# NANO_STM32F103_1.net
KiCad netlist of a schematic drawn in Altium Designer
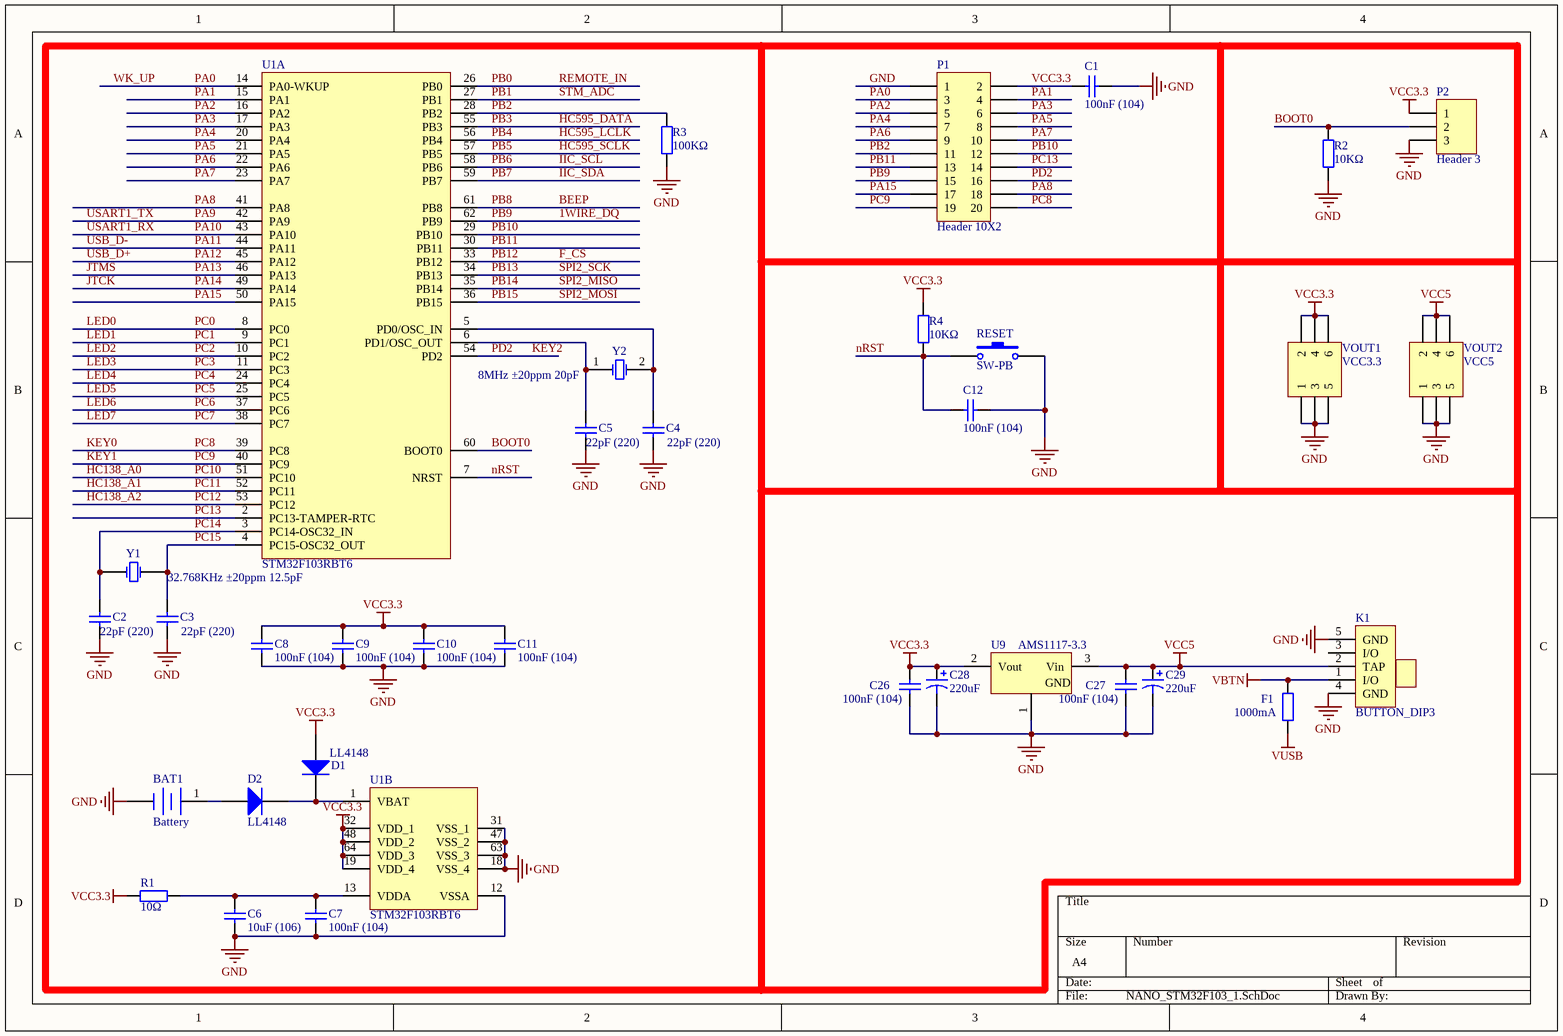
[diagram p0: NANO_STM32F103_1.SchDoc]

(export (version "E")
  (design (tool "Eeschema 10.0.6"))
  (components
    (comp (ref "BAT1")
      (value "Battery")
      (footprint "NANO_STM32F103:BAT-2")
      (description "Multicell Battery")
      (fields (field (name "PUBLISHER") "Altium Limited"))
      (libsource (lib "Miscellaneous Devices") (part "Battery"))
    )
    (comp (ref "C1")
      (value "100nF (104)")
      (footprint "NANO_STM32F103:0603_C")
      (description "贴片电容")
      (libsource (lib "Miscellaneous Devices LC") (part "0603 100nF (104) 10% 50V"))
    )
    (comp (ref "C2")
      (value "22pF (220)")
      (footprint "NANO_STM32F103:0603_C")
      (description "贴片电容")
      (libsource (lib "Miscellaneous Devices LC") (part "0603 22pF (220) 5% 50V"))
    )
    (comp (ref "C3")
      (value "22pF (220)")
      (footprint "NANO_STM32F103:0603_C")
      (description "贴片电容")
      (libsource (lib "Miscellaneous Devices LC") (part "0603 22pF (220) 5% 50V"))
    )
    (comp (ref "C4")
      (value "22pF (220)")
      (footprint "NANO_STM32F103:0603_C")
      (description "贴片电容")
      (libsource (lib "Miscellaneous Devices LC") (part "0603 22pF (220) 5% 50V"))
    )
    (comp (ref "C5")
      (value "22pF (220)")
      (footprint "NANO_STM32F103:0603_C")
      (description "贴片电容")
      (libsource (lib "Miscellaneous Devices LC") (part "0603 22pF (220) 5% 50V"))
    )
    (comp (ref "C6")
      (value "10uF (106)")
      (footprint "NANO_STM32F103:0805_C")
      (description "贴片电容")
      (libsource (lib "Miscellaneous Devices LC") (part "0805 10uF (106) 10% 25V"))
    )
    (comp (ref "C7")
      (value "100nF (104)")
      (footprint "NANO_STM32F103:0603_C")
      (description "贴片电容")
      (libsource (lib "Miscellaneous Devices LC") (part "0603 100nF (104) 10% 50V"))
    )
    (comp (ref "C8")
      (value "100nF (104)")
      (footprint "NANO_STM32F103:0603_C")
      (description "贴片电容")
      (libsource (lib "Miscellaneous Devices LC") (part "0603 100nF (104) 10% 50V"))
    )
    (comp (ref "C9")
      (value "100nF (104)")
      (footprint "NANO_STM32F103:0603_C")
      (description "贴片电容")
      (libsource (lib "Miscellaneous Devices LC") (part "0603 100nF (104) 10% 50V"))
    )
    (comp (ref "C10")
      (value "100nF (104)")
      (footprint "NANO_STM32F103:0603_C")
      (description "贴片电容")
      (libsource (lib "Miscellaneous Devices LC") (part "0603 100nF (104) 10% 50V"))
    )
    (comp (ref "C11")
      (value "100nF (104)")
      (footprint "NANO_STM32F103:0603_C")
      (description "贴片电容")
      (libsource (lib "Miscellaneous Devices LC") (part "0603 100nF (104) 10% 50V"))
    )
    (comp (ref "C12")
      (value "100nF (104)")
      (footprint "NANO_STM32F103:0603_C")
      (description "贴片电容")
      (libsource (lib "Miscellaneous Devices LC") (part "0603 100nF (104) 10% 50V"))
    )
    (comp (ref "C26")
      (value "100nF (104)")
      (footprint "NANO_STM32F103:0603_C")
      (description "贴片电容")
      (libsource (lib "Miscellaneous Devices LC") (part "0603 100nF (104) 10% 50V"))
    )
    (comp (ref "C27")
      (value "100nF (104)")
      (footprint "NANO_STM32F103:0603_C")
      (description "贴片电容")
      (libsource (lib "Miscellaneous Devices LC") (part "0603 100nF (104) 10% 50V"))
    )
    (comp (ref "C28")
      (value "220uF")
      (footprint "NANO_STM32F103:RB7.6-15")
      (description "电解电容")
      (fields (field (name "PUBLISHER") "Altium Limited"))
      (libsource (lib "Miscellaneous Devices") (part "Cap Pol1"))
    )
    (comp (ref "C29")
      (value "220uF")
      (footprint "NANO_STM32F103:RB7.6-15")
      (description "电解电容")
      (fields (field (name "PUBLISHER") "Altium Limited"))
      (libsource (lib "Miscellaneous Devices") (part "Cap Pol1"))
    )
    (comp (ref "D1")
      (value "LL4148")
      (footprint "NANO_STM32F103:LL-34")
      (description "开关二极管")
      (libsource (lib "Miscellaneous Devices LC") (part "LL-34 LL4148 LL-34 1206"))
    )
    (comp (ref "D2")
      (value "LL4148")
      (footprint "NANO_STM32F103:LL-34")
      (description "开关二极管")
      (libsource (lib "Miscellaneous Devices LC") (part "LL-34 LL4148 LL-34 1206"))
    )
    (comp (ref "F1")
      (value "1000mA")
      (footprint "NANO_STM32F103:0805_R")
      (description "自恢复保险丝")
      (libsource (lib "Miscellaneous Devices LC") (part "0805 1KΩ (1001) 1%"))
    )
    (comp (ref "K1")
      (value "BUTTON_DIP3")
      (footprint "NANO_STM32F103:SW")
      (description "拨动开关")
      (libsource (lib "NANO_STM32F103") (part "BUTTON_DIP3"))
    )
    (comp (ref "P1")
      (value "Header 10X2")
      (footprint "NANO_STM32F103:HDR2X10")
      (description "Header, 10-Pin, Dual row")
      (fields (field (name "PUBLISHER") "Altium Limited"))
      (libsource (lib "Miscellaneous Connectors") (part "Header 10X2"))
    )
    (comp (ref "P2")
      (value "Header 3")
      (footprint "NANO_STM32F103:HDR1X3")
      (description "Header, 3-Pin")
      (fields (field (name "PUBLISHER") "Altium Limited"))
      (libsource (lib "Miscellaneous Connectors") (part "Header 3"))
    )
    (comp (ref "R1")
      (value "10Ω")
      (footprint "NANO_STM32F103:0603_R")
      (description "贴片电阻")
      (libsource (lib "Miscellaneous Devices LC") (part "0603 10Ω (10R0) 1%"))
    )
    (comp (ref "R2")
      (value "10KΩ")
      (footprint "0603_R")
      (description "贴片电阻")
      (libsource (lib "NANO_STM32F103_2") (part "0603 10KΩ (1002) 1%"))
    )
    (comp (ref "R3")
      (value "100KΩ")
      (footprint "NANO_STM32F103:0603_R")
      (description "贴片电阻")
      (libsource (lib "Miscellaneous Devices LC") (part "0603 100KΩ (1003) 1%"))
    )
    (comp (ref "R4")
      (value "10KΩ")
      (footprint "NANO_STM32F103:0603_R")
      (description "贴片电阻")
      (libsource (lib "Miscellaneous Devices LC") (part "0603 10KΩ (1002) 1%"))
    )
    (comp (ref "RESET")
      (value "SW-PB")
      (footprint "NANO_STM32F103:SPST-2")
      (description "RESET")
      (fields (field (name "PUBLISHER") "Altium Limited"))
      (libsource (lib "Miscellaneous Devices") (part "SW-PB"))
    )
    (comp (ref "U1")
      (value "STM32F103RBT6")
      (footprint "NANO_STM32F103:LQFP-64_10x10x05P")
      (description "ARM")
      (libsource (lib "Miscellaneous Devices LC") (part "STM32F103RBT6"))
    )
    (comp (ref "U9")
      (value "AMS1117-3.3")
      (footprint "NANO_STM32F103:SOT-223")
      (description "低压差线性稳压(LDO)")
      (libsource (lib "Miscellaneous Devices LC") (part "SOT-223 AMS1117-3.3"))
    )
    (comp (ref "VOUT1")
      (value "VCC3.3")
      (footprint "NANO_STM32F103:HDR2X3")
      (description "Header, 3-Pin, Dual row")
      (fields (field (name "PUBLISHER") "Altium Limited"))
      (libsource (lib "Miscellaneous Connectors") (part "Header 3X2"))
    )
    (comp (ref "VOUT2")
      (value "VCC5")
      (footprint "NANO_STM32F103:HDR2X3")
      (description "Header, 3-Pin, Dual row")
      (fields (field (name "PUBLISHER") "Altium Limited"))
      (libsource (lib "Miscellaneous Connectors") (part "Header 3X2"))
    )
    (comp (ref "Y1")
      (value "32.768KHz ±20ppm 12.5pF")
      (footprint "NANO_STM32F103:SMD-3215_2P FC - 135")
      (description "贴片晶振")
      (libsource (lib "Miscellaneous Devices LC") (part "SMD-3215_2P 32.768KHz 20ppm 12.5pF"))
    )
    (comp (ref "Y2")
      (value "8MHz ±20ppm 20pF")
      (footprint "NANO_STM32F103:SMD-5032_2P")
      (description "贴片晶振")
      (libsource (lib "Miscellaneous Devices LC") (part "SMD-5032_2P 8MHz 20ppm 20pF"))
    )
  )
  (nets
    (net (code "1") (name "/1WIRE_DQ") (class "Default")
      (node (ref "P1") (pin "15") (pinfunction "15_15") (pintype "passive"))
      (node (ref "U1") (pin "62") (pinfunction "PB9_62") (pintype "passive"))
    )
    (net (code "2") (name "/BEEP") (class "Default")
      (node (ref "U1") (pin "61") (pinfunction "PB8_61") (pintype "passive"))
    )
    (net (code "3") (name "/BOOT0") (class "Default")
      (node (ref "P2") (pin "2") (pinfunction "2_2") (pintype "passive"))
      (node (ref "R2") (pin "2") (pinfunction "2_2") (pintype "passive"))
      (node (ref "U1") (pin "60") (pinfunction "BOOT0_60") (pintype "passive"))
    )
    (net (code "4") (name "/F_CS") (class "Default")
      (node (ref "U1") (pin "33") (pinfunction "PB12_33") (pintype "passive"))
    )
    (net (code "5") (name "/HC138_A0") (class "Default")
      (node (ref "U1") (pin "51") (pinfunction "PC10_51") (pintype "passive"))
    )
    (net (code "6") (name "/HC138_A1") (class "Default")
      (node (ref "U1") (pin "52") (pinfunction "PC11_52") (pintype "passive"))
    )
    (net (code "7") (name "/HC138_A2") (class "Default")
      (node (ref "U1") (pin "53") (pinfunction "PC12_53") (pintype "passive"))
    )
    (net (code "8") (name "/HC595_DATA") (class "Default")
      (node (ref "U1") (pin "55") (pinfunction "PB3_55") (pintype "passive"))
    )
    (net (code "9") (name "/HC595_LCLK") (class "Default")
      (node (ref "U1") (pin "56") (pinfunction "PB4_56") (pintype "passive"))
    )
    (net (code "10") (name "/HC595_SCLK") (class "Default")
      (node (ref "U1") (pin "57") (pinfunction "PB5_57") (pintype "passive"))
    )
    (net (code "11") (name "/IIC_SCL") (class "Default")
      (node (ref "U1") (pin "58") (pinfunction "PB6_58") (pintype "passive"))
    )
    (net (code "12") (name "/IIC_SDA") (class "Default")
      (node (ref "U1") (pin "59") (pinfunction "PB7_59") (pintype "passive"))
    )
    (net (code "13") (name "/JTCK") (class "Default")
      (node (ref "U1") (pin "49") (pinfunction "PA14_49") (pintype "passive"))
    )
    (net (code "14") (name "/JTMS") (class "Default")
      (node (ref "U1") (pin "46") (pinfunction "PA13_46") (pintype "passive"))
    )
    (net (code "15") (name "/KEY0") (class "Default")
      (node (ref "P1") (pin "20") (pinfunction "20_20") (pintype "passive"))
      (node (ref "U1") (pin "39") (pinfunction "PC8_39") (pintype "passive"))
    )
    (net (code "16") (name "/KEY1") (class "Default")
      (node (ref "P1") (pin "19") (pinfunction "19_19") (pintype "passive"))
      (node (ref "U1") (pin "40") (pinfunction "PC9_40") (pintype "passive"))
    )
    (net (code "17") (name "/KEY2") (class "Default")
      (node (ref "P1") (pin "16") (pinfunction "16_16") (pintype "passive"))
      (node (ref "U1") (pin "54") (pinfunction "PD2_54") (pintype "passive"))
    )
    (net (code "18") (name "/LED0") (class "Default")
      (node (ref "U1") (pin "8") (pinfunction "PC0_8") (pintype "passive"))
    )
    (net (code "19") (name "/LED1") (class "Default")
      (node (ref "U1") (pin "9") (pinfunction "PC1_9") (pintype "passive"))
    )
    (net (code "20") (name "/LED2") (class "Default")
      (node (ref "U1") (pin "10") (pinfunction "PC2_10") (pintype "passive"))
    )
    (net (code "21") (name "/LED3") (class "Default")
      (node (ref "U1") (pin "11") (pinfunction "PC3_11") (pintype "passive"))
    )
    (net (code "22") (name "/LED4") (class "Default")
      (node (ref "U1") (pin "24") (pinfunction "PC4_24") (pintype "passive"))
    )
    (net (code "23") (name "/LED5") (class "Default")
      (node (ref "U1") (pin "25") (pinfunction "PC5_25") (pintype "passive"))
    )
    (net (code "24") (name "/LED6") (class "Default")
      (node (ref "U1") (pin "37") (pinfunction "PC6_37") (pintype "passive"))
    )
    (net (code "25") (name "/LED7") (class "Default")
      (node (ref "U1") (pin "38") (pinfunction "PC7_38") (pintype "passive"))
    )
    (net (code "26") (name "/PA0") (class "Default")
      (node (ref "P1") (pin "3") (pinfunction "3_3") (pintype "passive"))
      (node (ref "U1") (pin "14") (pinfunction "PA0-WKUP_14") (pintype "passive"))
    )
    (net (code "27") (name "/PA1") (class "Default")
      (node (ref "P1") (pin "4") (pinfunction "4_4") (pintype "passive"))
      (node (ref "U1") (pin "15") (pinfunction "PA1_15") (pintype "passive"))
    )
    (net (code "28") (name "/PA2") (class "Default")
      (node (ref "P1") (pin "5") (pinfunction "5_5") (pintype "passive"))
      (node (ref "U1") (pin "16") (pinfunction "PA2_16") (pintype "passive"))
    )
    (net (code "29") (name "/PA3") (class "Default")
      (node (ref "P1") (pin "6") (pinfunction "6_6") (pintype "passive"))
      (node (ref "U1") (pin "17") (pinfunction "PA3_17") (pintype "passive"))
    )
    (net (code "30") (name "/PA4") (class "Default")
      (node (ref "P1") (pin "7") (pinfunction "7_7") (pintype "passive"))
      (node (ref "U1") (pin "20") (pinfunction "PA4_20") (pintype "passive"))
    )
    (net (code "31") (name "/PA5") (class "Default")
      (node (ref "P1") (pin "8") (pinfunction "8_8") (pintype "passive"))
      (node (ref "U1") (pin "21") (pinfunction "PA5_21") (pintype "passive"))
    )
    (net (code "32") (name "/PA6") (class "Default")
      (node (ref "P1") (pin "9") (pinfunction "9_9") (pintype "passive"))
      (node (ref "U1") (pin "22") (pinfunction "PA6_22") (pintype "passive"))
    )
    (net (code "33") (name "/PA7") (class "Default")
      (node (ref "P1") (pin "10") (pinfunction "10_10") (pintype "passive"))
      (node (ref "U1") (pin "23") (pinfunction "PA7_23") (pintype "passive"))
    )
    (net (code "34") (name "/PA8") (class "Default")
      (node (ref "P1") (pin "18") (pinfunction "18_18") (pintype "passive"))
      (node (ref "U1") (pin "41") (pinfunction "PA8_41") (pintype "passive"))
    )
    (net (code "35") (name "/PA9") (class "Default")
      (node (ref "U1") (pin "42") (pinfunction "PA9_42") (pintype "passive"))
    )
    (net (code "36") (name "/PA10") (class "Default")
      (node (ref "U1") (pin "43") (pinfunction "PA10_43") (pintype "passive"))
    )
    (net (code "37") (name "/PA11") (class "Default")
      (node (ref "U1") (pin "44") (pinfunction "PA11_44") (pintype "passive"))
    )
    (net (code "38") (name "/PA12") (class "Default")
      (node (ref "U1") (pin "45") (pinfunction "PA12_45") (pintype "passive"))
    )
    (net (code "39") (name "/PA15") (class "Default")
      (node (ref "P1") (pin "17") (pinfunction "17_17") (pintype "passive"))
      (node (ref "U1") (pin "50") (pinfunction "PA15_50") (pintype "passive"))
    )
    (net (code "40") (name "/PB0") (class "Default")
      (node (ref "U1") (pin "26") (pinfunction "PB0_26") (pintype "passive"))
    )
    (net (code "41") (name "/PB1") (class "Default")
      (node (ref "U1") (pin "27") (pinfunction "PB1_27") (pintype "passive"))
    )
    (net (code "42") (name "/PB2") (class "Default")
      (node (ref "P1") (pin "11") (pinfunction "11_11") (pintype "passive"))
      (node (ref "R3") (pin "2") (pinfunction "2_2") (pintype "passive"))
      (node (ref "U1") (pin "28") (pinfunction "PB2_28") (pintype "passive"))
    )
    (net (code "43") (name "/PB10") (class "Default")
      (node (ref "P1") (pin "12") (pinfunction "12_12") (pintype "passive"))
      (node (ref "U1") (pin "29") (pinfunction "PB10_29") (pintype "passive"))
    )
    (net (code "44") (name "/PB11") (class "Default")
      (node (ref "P1") (pin "13") (pinfunction "13_13") (pintype "passive"))
      (node (ref "U1") (pin "30") (pinfunction "PB11_30") (pintype "passive"))
    )
    (net (code "45") (name "/PB13") (class "Default")
      (node (ref "U1") (pin "34") (pinfunction "PB13_34") (pintype "passive"))
    )
    (net (code "46") (name "/PB14") (class "Default")
      (node (ref "U1") (pin "35") (pinfunction "PB14_35") (pintype "passive"))
    )
    (net (code "47") (name "/PB15") (class "Default")
      (node (ref "U1") (pin "36") (pinfunction "PB15_36") (pintype "passive"))
    )
    (net (code "48") (name "/PC13") (class "Default")
      (node (ref "P1") (pin "14") (pinfunction "14_14") (pintype "passive"))
      (node (ref "U1") (pin "2") (pinfunction "PC13-TAMPER-RTC_2") (pintype "passive"))
    )
    (net (code "49") (name "/PC14") (class "Default")
      (node (ref "C2") (pin "1") (pinfunction "1_1") (pintype "passive"))
      (node (ref "U1") (pin "3") (pinfunction "PC14-OSC32_IN_3") (pintype "passive"))
      (node (ref "Y1") (pin "2") (pinfunction "OSC2_2") (pintype "passive"))
    )
    (net (code "50") (name "/PC15") (class "Default")
      (node (ref "C3") (pin "2") (pinfunction "2_2") (pintype "passive"))
      (node (ref "U1") (pin "4") (pinfunction "PC15-OSC32_OUT_4") (pintype "passive"))
      (node (ref "Y1") (pin "1") (pinfunction "OSC1_1") (pintype "passive"))
    )
    (net (code "51") (name "/nRST") (class "Default")
      (node (ref "C12") (pin "2") (pinfunction "2_2") (pintype "passive"))
      (node (ref "R4") (pin "1") (pinfunction "1_1") (pintype "passive"))
      (node (ref "RESET") (pin "1") (pinfunction "1_1") (pintype "passive"))
      (node (ref "U1") (pin "7") (pinfunction "NRST_7") (pintype "passive"))
    )
    (net (code "52") (name "GND") (class "Default")
      (node (ref "BAT1") (pin "2") (pinfunction "-_2") (pintype "passive"))
      (node (ref "C1") (pin "1") (pinfunction "1_1") (pintype "passive"))
      (node (ref "C10") (pin "1") (pinfunction "1_1") (pintype "passive"))
      (node (ref "C11") (pin "1") (pinfunction "1_1") (pintype "passive"))
      (node (ref "C12") (pin "1") (pinfunction "1_1") (pintype "passive"))
      (node (ref "C2") (pin "2") (pinfunction "2_2") (pintype "passive"))
      (node (ref "C26") (pin "1") (pinfunction "1_1") (pintype "passive"))
      (node (ref "C27") (pin "1") (pinfunction "1_1") (pintype "passive"))
      (node (ref "C28") (pin "2") (pinfunction "2_2") (pintype "passive"))
      (node (ref "C29") (pin "2") (pinfunction "2_2") (pintype "passive"))
      (node (ref "C3") (pin "1") (pinfunction "1_1") (pintype "passive"))
      (node (ref "C4") (pin "1") (pinfunction "1_1") (pintype "passive"))
      (node (ref "C5") (pin "1") (pinfunction "1_1") (pintype "passive"))
      (node (ref "C6") (pin "2") (pinfunction "2_2") (pintype "passive"))
      (node (ref "C7") (pin "2") (pinfunction "2_2") (pintype "passive"))
      (node (ref "C8") (pin "1") (pinfunction "1_1") (pintype "passive"))
      (node (ref "C9") (pin "1") (pinfunction "1_1") (pintype "passive"))
      (node (ref "K1") (pin "4") (pinfunction "GND_4") (pintype "passive"))
      (node (ref "K1") (pin "5") (pinfunction "GND_5") (pintype "passive"))
      (node (ref "P1") (pin "1") (pinfunction "1_1") (pintype "passive"))
      (node (ref "P2") (pin "3") (pinfunction "3_3") (pintype "passive"))
      (node (ref "R2") (pin "1") (pinfunction "1_1") (pintype "passive"))
      (node (ref "R3") (pin "1") (pinfunction "1_1") (pintype "passive"))
      (node (ref "RESET") (pin "2") (pinfunction "2_2") (pintype "passive"))
      (node (ref "U1") (pin "12") (pinfunction "VSSA_12") (pintype "power_in"))
      (node (ref "U1") (pin "18") (pinfunction "VSS_4_18") (pintype "power_in"))
      (node (ref "U1") (pin "31") (pinfunction "VSS_1_31") (pintype "power_in"))
      (node (ref "U1") (pin "47") (pinfunction "VSS_2_47") (pintype "power_in"))
      (node (ref "U1") (pin "63") (pinfunction "VSS_3_63") (pintype "power_in"))
      (node (ref "U9") (pin "1") (pinfunction "GND_1") (pintype "passive"))
      (node (ref "VOUT1") (pin "1") (pinfunction "1_1") (pintype "passive"))
      (node (ref "VOUT1") (pin "3") (pinfunction "3_3") (pintype "passive"))
      (node (ref "VOUT1") (pin "5") (pinfunction "5_5") (pintype "passive"))
      (node (ref "VOUT2") (pin "1") (pinfunction "1_1") (pintype "passive"))
      (node (ref "VOUT2") (pin "3") (pinfunction "3_3") (pintype "passive"))
      (node (ref "VOUT2") (pin "5") (pinfunction "5_5") (pintype "passive"))
    )
    (net (code "53") (name "Net-(BAT1-+)") (class "Default")
      (node (ref "BAT1") (pin "1") (pinfunction "+_1") (pintype "passive"))
      (node (ref "D2") (pin "1") (pinfunction "A_1") (pintype "passive"))
    )
    (net (code "54") (name "Net-(D1-K)") (class "Default")
      (node (ref "D1") (pin "2") (pinfunction "K_2") (pintype "passive"))
      (node (ref "D2") (pin "2") (pinfunction "K_2") (pintype "passive"))
      (node (ref "U1") (pin "1") (pinfunction "VBAT_1") (pintype "power_in"))
    )
    (net (code "55") (name "Net-(U1A-PD0{slash}OSC_IN)") (class "Default")
      (node (ref "C4") (pin "2") (pinfunction "2_2") (pintype "passive"))
      (node (ref "U1") (pin "5") (pinfunction "PD0/OSC_IN_5") (pintype "passive"))
      (node (ref "Y2") (pin "2") (pinfunction "OSC2_2") (pintype "passive"))
    )
    (net (code "56") (name "Net-(U1A-PD1{slash}OSC_OUT)") (class "Default")
      (node (ref "C5") (pin "2") (pinfunction "2_2") (pintype "passive"))
      (node (ref "U1") (pin "6") (pinfunction "PD1/OSC_OUT_6") (pintype "passive"))
      (node (ref "Y2") (pin "1") (pinfunction "OSC1_1") (pintype "passive"))
    )
    (net (code "57") (name "Net-(U1B-VDDA)") (class "Default")
      (node (ref "C6") (pin "1") (pinfunction "1_1") (pintype "passive"))
      (node (ref "C7") (pin "1") (pinfunction "1_1") (pintype "passive"))
      (node (ref "R1") (pin "2") (pinfunction "2_2") (pintype "passive"))
      (node (ref "U1") (pin "13") (pinfunction "VDDA_13") (pintype "power_in"))
    )
    (net (code "58") (name "VBTN") (class "Default")
      (node (ref "F1") (pin "2") (pinfunction "2_2") (pintype "passive"))
      (node (ref "K1") (pin "1") (pinfunction "I/O_1") (pintype "passive"))
    )
    (net (code "59") (name "VCC3.3") (class "Default")
      (node (ref "C1") (pin "2") (pinfunction "2_2") (pintype "passive"))
      (node (ref "C10") (pin "2") (pinfunction "2_2") (pintype "passive"))
      (node (ref "C11") (pin "2") (pinfunction "2_2") (pintype "passive"))
      (node (ref "C26") (pin "2") (pinfunction "2_2") (pintype "passive"))
      (node (ref "C28") (pin "1") (pinfunction "1_1") (pintype "passive"))
      (node (ref "C8") (pin "2") (pinfunction "2_2") (pintype "passive"))
      (node (ref "C9") (pin "2") (pinfunction "2_2") (pintype "passive"))
      (node (ref "D1") (pin "1") (pinfunction "A_1") (pintype "passive"))
      (node (ref "P1") (pin "2") (pinfunction "2_2") (pintype "passive"))
      (node (ref "P2") (pin "1") (pinfunction "1_1") (pintype "passive"))
      (node (ref "R1") (pin "1") (pinfunction "1_1") (pintype "passive"))
      (node (ref "R4") (pin "2") (pinfunction "2_2") (pintype "passive"))
      (node (ref "U1") (pin "19") (pinfunction "VDD_4_19") (pintype "power_in"))
      (node (ref "U1") (pin "32") (pinfunction "VDD_1_32") (pintype "power_in"))
      (node (ref "U1") (pin "48") (pinfunction "VDD_2_48") (pintype "power_in"))
      (node (ref "U1") (pin "64") (pinfunction "VDD_3_64") (pintype "power_in"))
      (node (ref "U9") (pin "2") (pinfunction "Vout_2") (pintype "passive"))
      (node (ref "VOUT1") (pin "2") (pinfunction "2_2") (pintype "passive"))
      (node (ref "VOUT1") (pin "4") (pinfunction "4_4") (pintype "passive"))
      (node (ref "VOUT1") (pin "6") (pinfunction "6_6") (pintype "passive"))
    )
    (net (code "60") (name "VCC5") (class "Default")
      (node (ref "C27") (pin "2") (pinfunction "2_2") (pintype "passive"))
      (node (ref "C29") (pin "1") (pinfunction "1_1") (pintype "passive"))
      (node (ref "K1") (pin "2") (pinfunction "TAP_2") (pintype "passive"))
      (node (ref "U9") (pin "3") (pinfunction "Vin_3") (pintype "passive"))
      (node (ref "VOUT2") (pin "2") (pinfunction "2_2") (pintype "passive"))
      (node (ref "VOUT2") (pin "4") (pinfunction "4_4") (pintype "passive"))
      (node (ref "VOUT2") (pin "6") (pinfunction "6_6") (pintype "passive"))
    )
    (net (code "61") (name "VUSB") (class "Default")
      (node (ref "F1") (pin "1") (pinfunction "1_1") (pintype "passive"))
    )
    (net (code "62") (name "unconnected-(K1-I{slash}O-Pad3)") (class "Default")
      (node (ref "K1") (pin "3") (pinfunction "I/O_3") (pintype "passive"))
    )
  )
)
